# USB3toSerial.net
KiCad netlist of a schematic drawn in Altium Designer
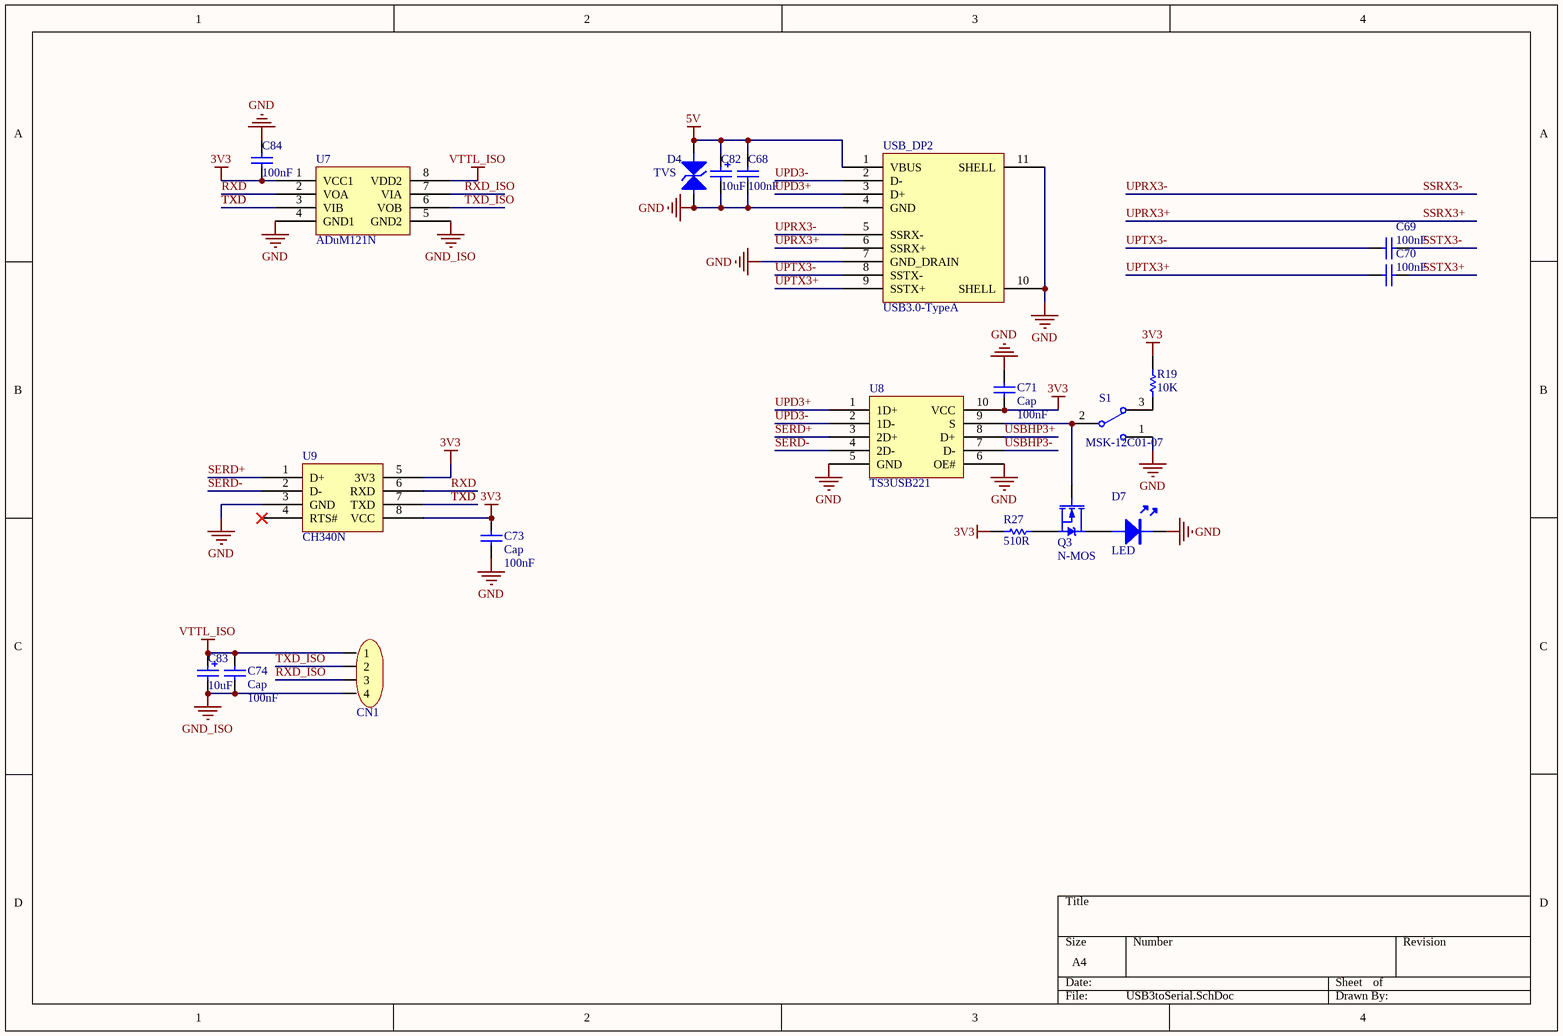
[diagram p0: USB3toSerial.SchDoc]

(export (version "E")
  (design (tool "Eeschema 10.0.6"))
  (components
    (comp (ref "C68")
      (value "100nF")
      (footprint "C0603_M")
      (description "Capacitor")
      (fields (field (name "Comment") "Cap") (field (name "PUBLISHER") "Altium Limited"))
      (libsource (lib "Miscellaneous Devices") (part "Cap"))
    )
    (comp (ref "C69")
      (value "100nF")
      (footprint "1.03-电容:C0402_M")
      (description "Capacitor")
      (fields (field (name "Comment") "Cap") (field (name "PUBLISHER") "Altium Limited"))
      (libsource (lib "Miscellaneous Devices") (part "Cap"))
    )
    (comp (ref "C70")
      (value "100nF")
      (footprint "1.03-电容:C0402_M")
      (description "Capacitor")
      (fields (field (name "Comment") "Cap") (field (name "PUBLISHER") "Altium Limited"))
      (libsource (lib "Miscellaneous Devices") (part "Cap"))
    )
    (comp (ref "C71")
      (value "Cap")
      (footprint "C0603_M")
      (description "Capacitor")
      (fields (field (name "ALTIUM_VALUE") "100nF") (field (name "PUBLISHER") "Altium Limited"))
      (libsource (lib "Miscellaneous Devices") (part "Cap"))
    )
    (comp (ref "C73")
      (value "Cap")
      (footprint "C0603_M")
      (description "Capacitor")
      (fields (field (name "ALTIUM_VALUE") "100nF") (field (name "PUBLISHER") "Altium Limited"))
      (libsource (lib "Miscellaneous Devices") (part "Cap"))
    )
    (comp (ref "C74")
      (value "Cap")
      (footprint "C0603_M")
      (description "Capacitor")
      (fields (field (name "ALTIUM_VALUE") "100nF") (field (name "PUBLISHER") "Altium Limited"))
      (libsource (lib "Miscellaneous Devices") (part "Cap"))
    )
    (comp (ref "C82")
      (value "10uF")
      (footprint "电容:TAJ-A/3216")
      (description "Polarized Capacitor (Axial)")
      (fields (field (name "Comment") "Cap Pol2") (field (name "PUBLISHER") "Altium Limited"))
      (libsource (lib "Miscellaneous Devices") (part "Cap Pol2"))
    )
    (comp (ref "C83")
      (value "10uF")
      (footprint "电容:TAJ-A/3216")
      (description "Polarized Capacitor (Axial)")
      (fields (field (name "Comment") "Cap Pol2") (field (name "PUBLISHER") "Altium Limited"))
      (libsource (lib "Miscellaneous Devices") (part "Cap Pol2"))
    )
    (comp (ref "C84")
      (value "100nF")
      (footprint "C0603_M")
      (description "Capacitor")
      (fields (field (name "Comment") "Cap") (field (name "PUBLISHER") "Altium Limited"))
      (libsource (lib "Miscellaneous Devices") (part "Cap"))
    )
    (comp (ref "CN1")
      (value "HDGC1002WR-S-4P")
      (footprint "4.08-XH2.54连接器:XH2.54-WI-4P")
      (fields (field (name "MANUFACTURER") "HDGC(华德共创)"))
      (libsource (lib "Connector") (part "4P端子不带固定脚"))
    )
    (comp (ref "D4")
      (value "TVS")
      (footprint "SOD-123")
      (description "双向瞬态抑制二极管")
      (libsource (lib "二极管") (part "TVS"))
    )
    (comp (ref "D7") (value "LED") (footprint "1.08-LED发光二极管:LED0402_B") (libsource (lib "LED") (part "LED")))
    (comp (ref "Q3")
      (value "N-MOS")
      (footprint "MyPCBLib:SOT-723_L1.2-W0.8-P0.40-LS1.2-BR")
      (description "N沟道场效应管")
      (libsource (lib "MOS管") (part "N-MOS"))
    )
    (comp (ref "R19")
      (value "10K")
      (footprint "R0603_M")
      (description "Resistor")
      (fields (field (name "Comment") "Res1") (field (name "PUBLISHER") "Altium Limited"))
      (libsource (lib "Miscellaneous Devices") (part "Res1"))
    )
    (comp (ref "R27")
      (value "510R")
      (footprint "R0603_M")
      (description "Resistor")
      (fields (field (name "Comment") "Res1") (field (name "PUBLISHER") "Altium Limited"))
      (libsource (lib "Miscellaneous Devices") (part "Res1"))
    )
    (comp (ref "S1")
      (value "MSK-12C01-07")
      (footprint "MSK-12C01-07")
      (libsource (lib "电源开关") (part "MSK-12C01-07"))
    )
    (comp (ref "U7")
      (value "ADuM121N")
      (footprint "2.00-DIP-SOP、SOIC、ESOP、TSSOP、ETSSOP封装:SOP8_M")
      (libsource (lib "MyIntLib") (part "ADuM121N"))
    )
    (comp (ref "U8")
      (value "TS3USB221")
      (footprint "UQFN-10_L2.0-W1.5-P0.50-BL")
      (libsource (lib "MyIntLib") (part "TS3USB221"))
    )
    (comp (ref "U9")
      (value "CH340N")
      (footprint "2.00-DIP-SOP、SOIC、ESOP、TSSOP、ETSSOP封装:SOP8_M")
      (libsource (lib "MyIntLib") (part "CH340N"))
    )
    (comp (ref "USB_DP2")
      (value "USB3.0-TypeA")
      (footprint "3.03-USB3.1 Type C-M.2-NGFF-HDMI-PCI-E接口:USB3.1 Type-A_DIP_F")
      (libsource (lib "MyIntLib") (part "USB3.0-TypeA"))
    )
  )
  (nets
    (net (code "1") (name "/RXD") (class "Default")
      (node (ref "U7") (pin "2") (pinfunction "VOA_2") (pintype "passive"))
      (node (ref "U9") (pin "6") (pinfunction "RXD_6") (pintype "passive"))
    )
    (net (code "2") (name "/RXD_ISO") (class "Default")
      (node (ref "CN1") (pin "3") (pinfunction "3_3") (pintype "passive"))
      (node (ref "U7") (pin "7") (pinfunction "VIA_7") (pintype "passive"))
    )
    (net (code "3") (name "/SERD+") (class "Default")
      (node (ref "U8") (pin "3") (pinfunction "2D+_3") (pintype "passive"))
      (node (ref "U9") (pin "1") (pinfunction "D+_1") (pintype "passive"))
    )
    (net (code "4") (name "/SERD-") (class "Default")
      (node (ref "U8") (pin "4") (pinfunction "2D-_4") (pintype "passive"))
      (node (ref "U9") (pin "2") (pinfunction "D-_2") (pintype "passive"))
    )
    (net (code "5") (name "/SSRX3+") (class "Default")
      (node (ref "USB_DP2") (pin "6") (pinfunction "SSRX+_6") (pintype "passive"))
    )
    (net (code "6") (name "/SSRX3-") (class "Default")
      (node (ref "USB_DP2") (pin "5") (pinfunction "SSRX-_5") (pintype "passive"))
    )
    (net (code "7") (name "/SSTX3+") (class "Default")
      (node (ref "C70") (pin "1") (pinfunction "1_1") (pintype "passive"))
    )
    (net (code "8") (name "/SSTX3-") (class "Default")
      (node (ref "C69") (pin "1") (pinfunction "1_1") (pintype "passive"))
    )
    (net (code "9") (name "/TXD") (class "Default")
      (node (ref "U7") (pin "3") (pinfunction "VIB_3") (pintype "passive"))
      (node (ref "U9") (pin "7") (pinfunction "TXD_7") (pintype "passive"))
    )
    (net (code "10") (name "/TXD_ISO") (class "Default")
      (node (ref "CN1") (pin "2") (pinfunction "2_2") (pintype "passive"))
      (node (ref "U7") (pin "6") (pinfunction "VOB_6") (pintype "passive"))
    )
    (net (code "11") (name "/UPD3+") (class "Default")
      (node (ref "U8") (pin "1") (pinfunction "1D+_1") (pintype "passive"))
      (node (ref "USB_DP2") (pin "3") (pinfunction "D+_3") (pintype "passive"))
    )
    (net (code "12") (name "/UPD3-") (class "Default")
      (node (ref "U8") (pin "2") (pinfunction "1D-_2") (pintype "passive"))
      (node (ref "USB_DP2") (pin "2") (pinfunction "D-_2") (pintype "passive"))
    )
    (net (code "13") (name "/UPTX3+") (class "Default")
      (node (ref "C70") (pin "2") (pinfunction "2_2") (pintype "passive"))
      (node (ref "USB_DP2") (pin "9") (pinfunction "SSTX+_9") (pintype "passive"))
    )
    (net (code "14") (name "/UPTX3-") (class "Default")
      (node (ref "C69") (pin "2") (pinfunction "2_2") (pintype "passive"))
      (node (ref "USB_DP2") (pin "8") (pinfunction "SSTX-_8") (pintype "passive"))
    )
    (net (code "15") (name "/USBHP3+") (class "Default")
      (node (ref "U8") (pin "8") (pinfunction "D+_8") (pintype "passive"))
    )
    (net (code "16") (name "/USBHP3-") (class "Default")
      (node (ref "U8") (pin "7") (pinfunction "D-_7") (pintype "passive"))
    )
    (net (code "17") (name "3V3") (class "Default")
      (node (ref "C71") (pin "1") (pinfunction "1_1") (pintype "passive"))
      (node (ref "C73") (pin "2") (pinfunction "2_2") (pintype "passive"))
      (node (ref "C84") (pin "1") (pinfunction "1_1") (pintype "passive"))
      (node (ref "R19") (pin "2") (pinfunction "2_2") (pintype "passive"))
      (node (ref "R27") (pin "2") (pinfunction "2_2") (pintype "passive"))
      (node (ref "U7") (pin "1") (pinfunction "VCC1_1") (pintype "passive"))
      (node (ref "U8") (pin "10") (pinfunction "VCC_10") (pintype "passive"))
      (node (ref "U9") (pin "5") (pinfunction "3V3_5") (pintype "passive"))
      (node (ref "U9") (pin "8") (pinfunction "VCC_8") (pintype "passive"))
    )
    (net (code "18") (name "5V") (class "Default")
      (node (ref "C68") (pin "2") (pinfunction "2_2") (pintype "passive"))
      (node (ref "C82") (pin "1") (pinfunction "1_1") (pintype "passive"))
      (node (ref "D4") (pin "K") (pinfunction "K_K") (pintype "passive"))
      (node (ref "USB_DP2") (pin "1") (pinfunction "VBUS_1") (pintype "passive"))
    )
    (net (code "19") (name "GND") (class "Default")
      (node (ref "C68") (pin "1") (pinfunction "1_1") (pintype "passive"))
      (node (ref "C71") (pin "2") (pinfunction "2_2") (pintype "passive"))
      (node (ref "C73") (pin "1") (pinfunction "1_1") (pintype "passive"))
      (node (ref "C82") (pin "2") (pinfunction "2_2") (pintype "passive"))
      (node (ref "C84") (pin "2") (pinfunction "2_2") (pintype "passive"))
      (node (ref "D4") (pin "A") (pinfunction "A_A") (pintype "passive"))
      (node (ref "D7") (pin "K") (pinfunction "K_K") (pintype "passive"))
      (node (ref "S1") (pin "1") (pinfunction "1_1") (pintype "passive"))
      (node (ref "U7") (pin "4") (pinfunction "GND1_4") (pintype "passive"))
      (node (ref "U8") (pin "5") (pinfunction "GND_5") (pintype "passive"))
      (node (ref "U8") (pin "6") (pinfunction "OE#_6") (pintype "passive"))
      (node (ref "U9") (pin "3") (pinfunction "GND_3") (pintype "passive"))
      (node (ref "USB_DP2") (pin "10") (pinfunction "SHELL_10") (pintype "passive"))
      (node (ref "USB_DP2") (pin "11") (pinfunction "SHELL_11") (pintype "passive"))
      (node (ref "USB_DP2") (pin "4") (pinfunction "GND_4") (pintype "passive"))
      (node (ref "USB_DP2") (pin "7") (pinfunction "GND_DRAIN_7") (pintype "passive"))
    )
    (net (code "20") (name "GND_ISO") (class "Default")
      (node (ref "C74") (pin "1") (pinfunction "1_1") (pintype "passive"))
      (node (ref "C83") (pin "2") (pinfunction "2_2") (pintype "passive"))
      (node (ref "CN1") (pin "4") (pinfunction "4_4") (pintype "passive"))
      (node (ref "U7") (pin "5") (pinfunction "GND2_5") (pintype "passive"))
    )
    (net (code "21") (name "Net-(D7-PadA)") (class "Default")
      (node (ref "D7") (pin "A") (pinfunction "A_A") (pintype "passive"))
      (node (ref "Q3") (pin "D") (pinfunction "D_D") (pintype "passive"))
    )
    (net (code "22") (name "Net-(Q3-PadS)") (class "Default")
      (node (ref "Q3") (pin "S") (pinfunction "S_S") (pintype "passive"))
      (node (ref "R27") (pin "1") (pinfunction "1_1") (pintype "passive"))
    )
    (net (code "23") (name "Net-(R19-Pad1)") (class "Default")
      (node (ref "R19") (pin "1") (pinfunction "1_1") (pintype "passive"))
      (node (ref "S1") (pin "3") (pinfunction "3_3") (pintype "passive"))
    )
    (net (code "24") (name "Net-(U8-S)") (class "Default")
      (node (ref "Q3") (pin "G") (pinfunction "G_G") (pintype "passive"))
      (node (ref "S1") (pin "2") (pinfunction "2_2") (pintype "passive"))
      (node (ref "U8") (pin "9") (pinfunction "S_9") (pintype "passive"))
    )
    (net (code "25") (name "VTTL_ISO") (class "Default")
      (node (ref "C74") (pin "2") (pinfunction "2_2") (pintype "passive"))
      (node (ref "C83") (pin "1") (pinfunction "1_1") (pintype "passive"))
      (node (ref "CN1") (pin "1") (pinfunction "1_1") (pintype "passive"))
      (node (ref "U7") (pin "8") (pinfunction "VDD2_8") (pintype "passive"))
    )
    (net (code "26") (name "unconnected-(U9-RTS#-Pad4)") (class "Default")
      (node (ref "U9") (pin "4") (pinfunction "RTS#_4") (pintype "passive+no_connect"))
    )
  )
)
